# adapter_stick.net
KiCad netlist of a schematic drawn in EAGLE
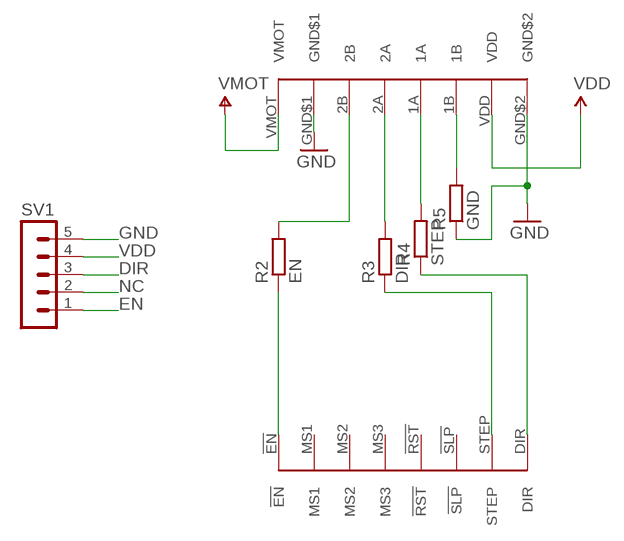
[diagram p0: schematic, sheet 1]

(export (version "E")
  (design (tool "Eeschema 10.0.6"))
  (components
    (comp (ref "J1X")
      (value "CLONOLU")
      (footprint "eagle-import:CLONOLU")
      (libsource (lib "eagle-import") (part "CLONOLU"))
    )
    (comp (ref "R2")
      (value "EN")
      (footprint "eagle-import:R0402")
      (libsource (lib "eagle-import") (part "R-EU_R0402"))
    )
    (comp (ref "R3")
      (value "DIR")
      (footprint "eagle-import:R0402")
      (libsource (lib "eagle-import") (part "R-EU_R0402"))
    )
    (comp (ref "R4")
      (value "STEP")
      (footprint "eagle-import:R0402")
      (libsource (lib "eagle-import") (part "R-EU_R0402"))
    )
    (comp (ref "R5")
      (value "GND")
      (footprint "eagle-import:R0402")
      (libsource (lib "eagle-import") (part "R-EU_R0402"))
    )
    (comp (ref "SV1")
      (value "MA05-1")
      (footprint "eagle-import:MA05-1")
      (libsource (lib "eagle-import") (part "MA05-1"))
    )
  )
  (nets
    (net (code "1") (name "/DIR") (class "Default")
      (node (ref "J1X") (pin "DIR") (pinfunction "DIR_DIR") (pintype "bidirectional"))
      (node (ref "R4") (pin "1") (pinfunction "1_1") (pintype "passive"))
      (node (ref "SV1") (pin "3") (pinfunction "3_3") (pintype "passive"))
    )
    (net (code "2") (name "/EN") (class "Default")
      (node (ref "J1X") (pin "!EN") (pinfunction "~{EN}_!EN") (pintype "bidirectional"))
      (node (ref "R2") (pin "1") (pinfunction "1_1") (pintype "passive"))
      (node (ref "SV1") (pin "1") (pinfunction "1_1") (pintype "passive"))
    )
    (net (code "3") (name "/NC") (class "Default")
      (node (ref "J1X") (pin "2A") (pinfunction "2A_2A") (pintype "bidirectional"))
      (node (ref "J1X") (pin "STEP") (pinfunction "STEP_STEP") (pintype "bidirectional"))
      (node (ref "R3") (pin "1") (pinfunction "1_1") (pintype "passive"))
      (node (ref "R3") (pin "2") (pinfunction "2_2") (pintype "passive"))
      (node (ref "SV1") (pin "2") (pinfunction "2_2") (pintype "passive"))
    )
    (net (code "4") (name "GND") (class "Default")
      (node (ref "J1X") (pin "GND$1") (pinfunction "GND$1_GND$1") (pintype "power_in"))
      (node (ref "J1X") (pin "GND$2") (pinfunction "GND$2_GND$2") (pintype "power_in"))
      (node (ref "R5") (pin "1") (pinfunction "1_1") (pintype "passive"))
      (node (ref "SV1") (pin "5") (pinfunction "5_5") (pintype "passive"))
    )
    (net (code "5") (name "Net-(J1X-Pad1A)") (class "Default")
      (node (ref "J1X") (pin "1A") (pinfunction "1A_1A") (pintype "bidirectional"))
      (node (ref "R4") (pin "2") (pinfunction "2_2") (pintype "passive"))
    )
    (net (code "6") (name "Net-(J1X-Pad1B)") (class "Default")
      (node (ref "J1X") (pin "1B") (pinfunction "1B_1B") (pintype "bidirectional"))
      (node (ref "R5") (pin "2") (pinfunction "2_2") (pintype "passive"))
    )
    (net (code "7") (name "Net-(J1X-Pad2B)") (class "Default")
      (node (ref "J1X") (pin "2B") (pinfunction "2B_2B") (pintype "bidirectional"))
      (node (ref "R2") (pin "2") (pinfunction "2_2") (pintype "passive"))
    )
    (net (code "8") (name "VDD") (class "Default")
      (node (ref "J1X") (pin "VDD") (pinfunction "VDD_VDD") (pintype "power_in"))
      (node (ref "SV1") (pin "4") (pinfunction "4_4") (pintype "passive"))
    )
    (net (code "9") (name "VMOT") (class "Default")
      (node (ref "J1X") (pin "VMOT") (pinfunction "VMOT_VMOT") (pintype "power_in"))
    )
    (net (code "10") (name "unconnected-(J1X-PadMS1)") (class "Default")
      (node (ref "J1X") (pin "MS1") (pinfunction "MS1_MS1") (pintype "bidirectional"))
    )
    (net (code "11") (name "unconnected-(J1X-PadMS2)") (class "Default")
      (node (ref "J1X") (pin "MS2") (pinfunction "MS2_MS2") (pintype "bidirectional"))
    )
    (net (code "12") (name "unconnected-(J1X-PadMS3)") (class "Default")
      (node (ref "J1X") (pin "MS3") (pinfunction "MS3_MS3") (pintype "bidirectional"))
    )
    (net (code "13") (name "unconnected-(J1XA-~{RST}-Pad!RST)") (class "Default")
      (node (ref "J1X") (pin "!RST") (pinfunction "~{RST}_!RST") (pintype "bidirectional"))
    )
    (net (code "14") (name "unconnected-(J1XA-~{SLP}-Pad!SLP)") (class "Default")
      (node (ref "J1X") (pin "!SLP") (pinfunction "~{SLP}_!SLP") (pintype "bidirectional"))
    )
  )
)
